# podfm.net
KiCad netlist of a schematic drawn in EAGLE
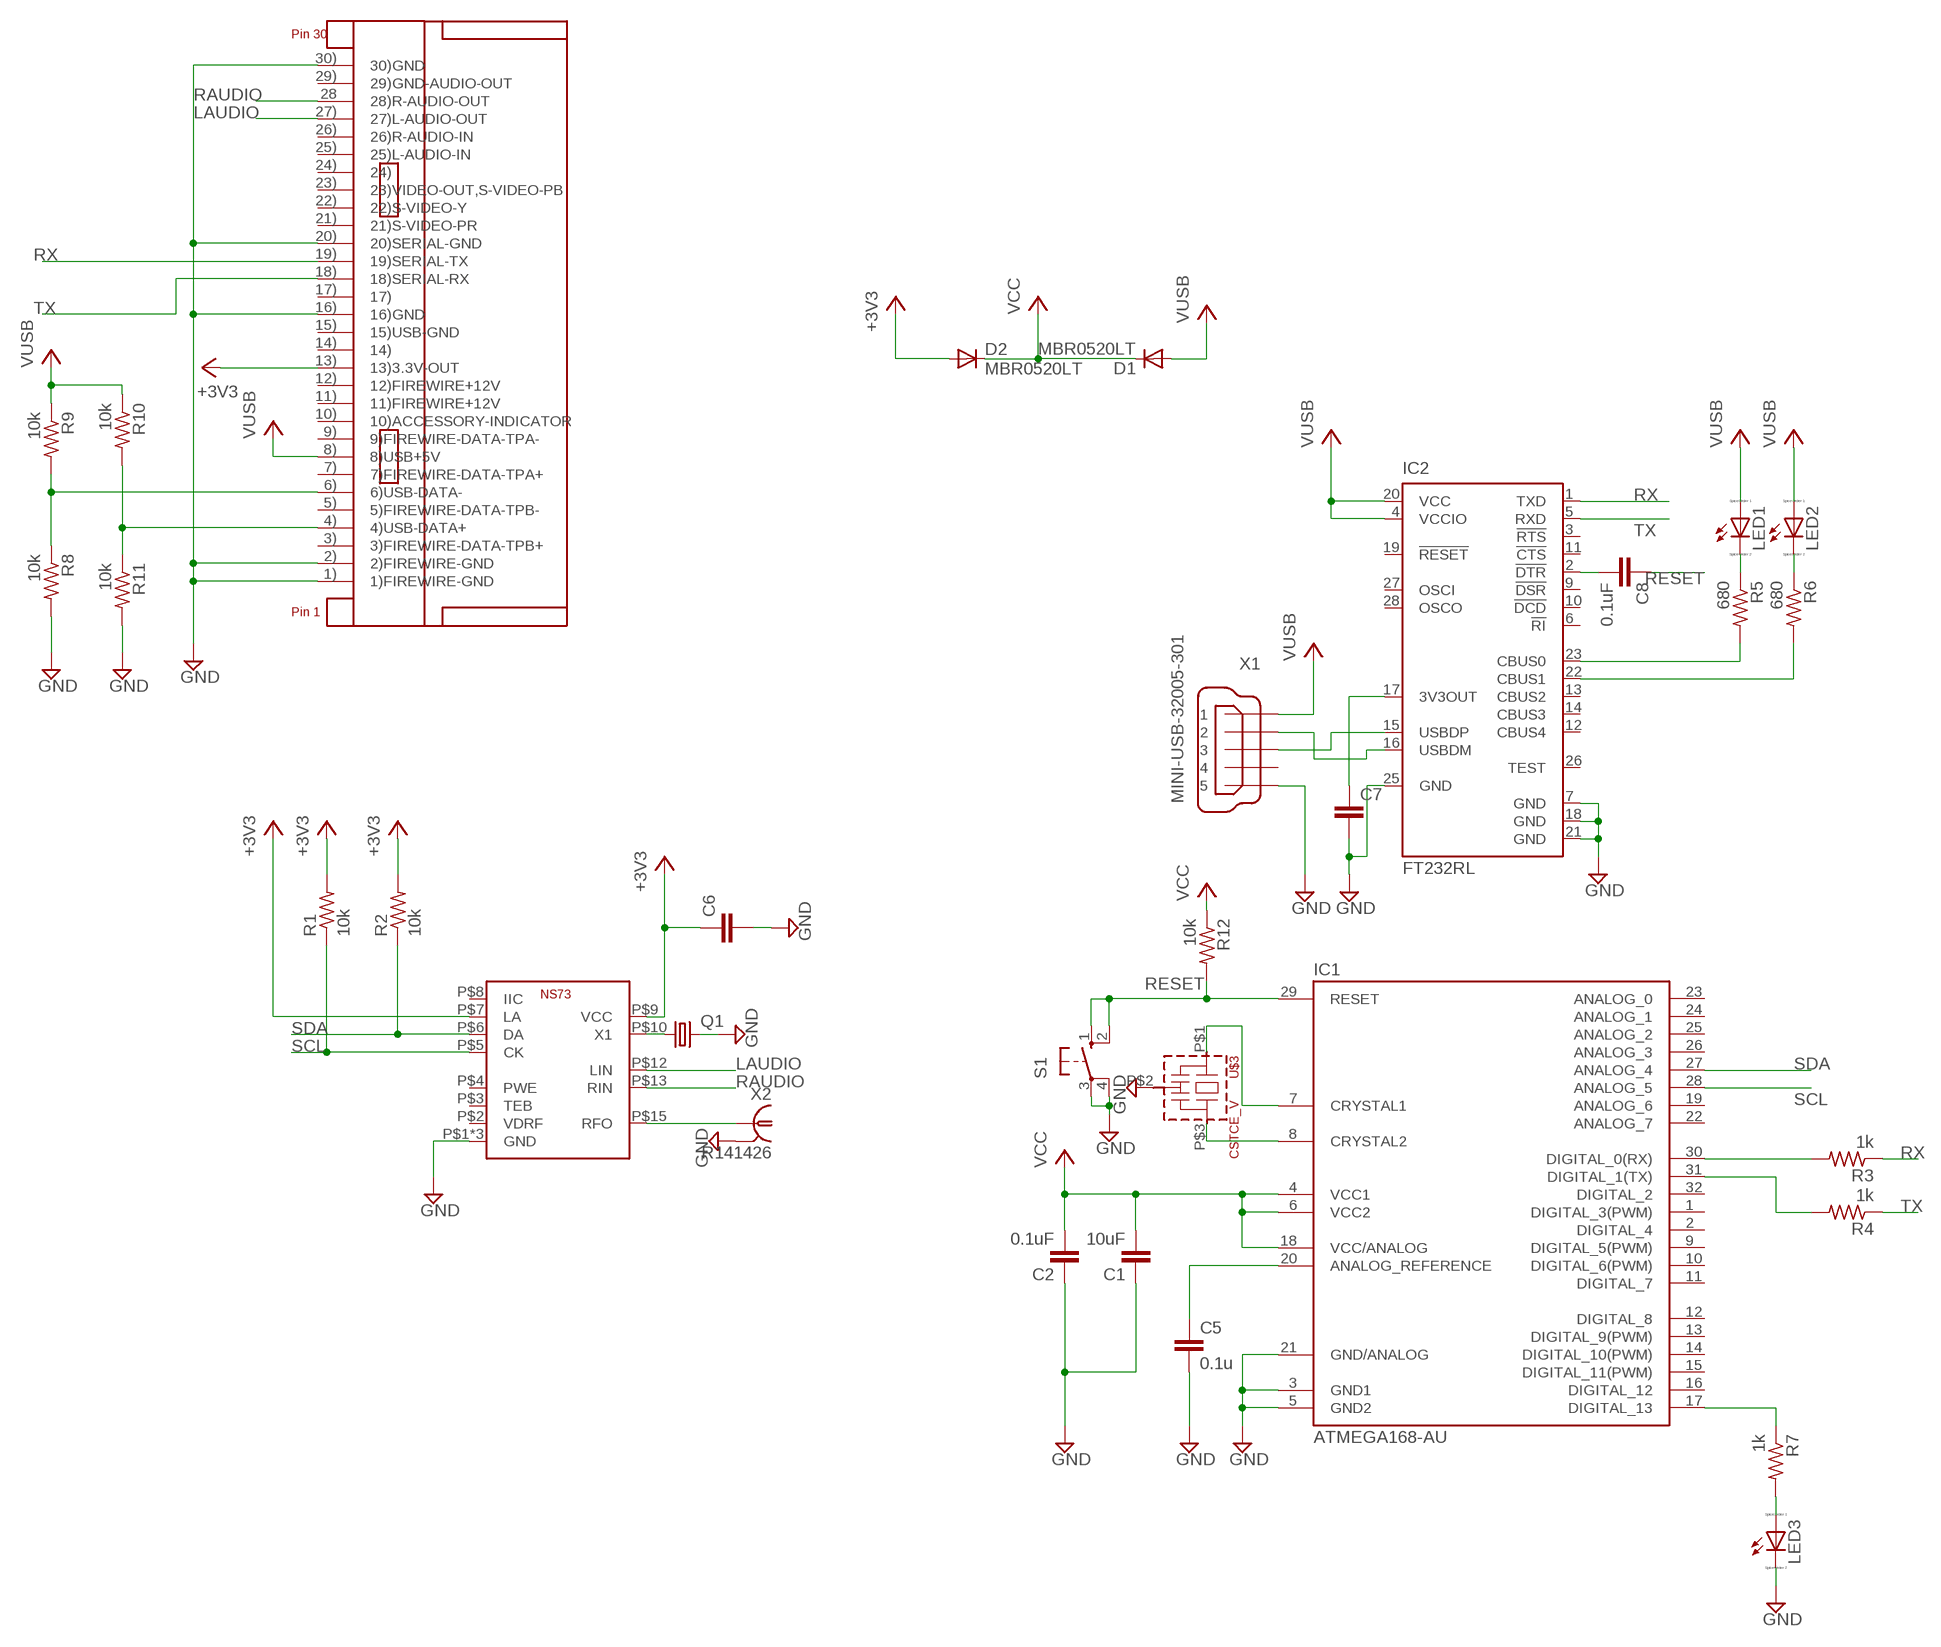
[diagram p0: schematic, sheet 1]

(export (version "E")
  (design (tool "Eeschema 10.0.6"))
  (components
    (comp (ref "C1")
      (value "10uF")
      (footprint "eagle-import:C1206")
      (libsource (lib "eagle-import") (part "C-EUC1206"))
    )
    (comp (ref "C2")
      (value "0.1uF")
      (footprint "eagle-import:C1206")
      (libsource (lib "eagle-import") (part "C-EUC1206"))
    )
    (comp (ref "C5")
      (value "0.1u")
      (footprint "eagle-import:C1206")
      (libsource (lib "eagle-import") (part "C-EUC1206"))
    )
    (comp (ref "C6")
      (value "C-EUC1206")
      (footprint "eagle-import:C1206")
      (libsource (lib "eagle-import") (part "C-EUC1206"))
    )
    (comp (ref "C7")
      (value "C-EUC1206")
      (footprint "eagle-import:C1206")
      (libsource (lib "eagle-import") (part "C-EUC1206"))
    )
    (comp (ref "C8")
      (value "0.1uF")
      (footprint "eagle-import:C1206")
      (libsource (lib "eagle-import") (part "C-EUC1206"))
    )
    (comp (ref "D1")
      (value "MBR0520LT")
      (footprint "eagle-import:SOD123")
      (libsource (lib "eagle-import") (part "MBR0520LT"))
    )
    (comp (ref "D2")
      (value "MBR0520LT")
      (footprint "eagle-import:SOD123")
      (libsource (lib "eagle-import") (part "MBR0520LT"))
    )
    (comp (ref "IC1")
      (value "ATMEGA168-AU")
      (footprint "eagle-import:TQFP32-08")
      (libsource (lib "eagle-import") (part "ATMEGA168-AU"))
    )
    (comp (ref "IC2")
      (value "FT232RL")
      (footprint "eagle-import:SSOP28")
      (libsource (lib "eagle-import") (part "FT232RL"))
    )
    (comp (ref "LED1")
      (value "LED_ESML0603")
      (footprint "eagle-import:LED_SML0603")
      (libsource (lib "eagle-import") (part "LED_ESML0603"))
    )
    (comp (ref "LED2")
      (value "LED_ESML0603")
      (footprint "eagle-import:LED_SML0603")
      (libsource (lib "eagle-import") (part "LED_ESML0603"))
    )
    (comp (ref "LED3")
      (value "LED_ESML0603")
      (footprint "eagle-import:LED_SML0603")
      (libsource (lib "eagle-import") (part "LED_ESML0603"))
    )
    (comp (ref "Q1")
      (value "CRYSTALTC26H")
      (footprint "eagle-import:TC26H")
      (libsource (lib "eagle-import") (part "CRYSTALTC26H"))
    )
    (comp (ref "R1")
      (value "10k")
      (footprint "eagle-import:R1206")
      (libsource (lib "eagle-import") (part "R-US_R1206"))
    )
    (comp (ref "R2")
      (value "10k")
      (footprint "eagle-import:R1206")
      (libsource (lib "eagle-import") (part "R-US_R1206"))
    )
    (comp (ref "R3")
      (value "1k")
      (footprint "eagle-import:R1206")
      (libsource (lib "eagle-import") (part "R-US_R1206"))
    )
    (comp (ref "R4")
      (value "1k")
      (footprint "eagle-import:R1206")
      (libsource (lib "eagle-import") (part "R-US_R1206"))
    )
    (comp (ref "R5")
      (value "680")
      (footprint "eagle-import:R0805")
      (libsource (lib "eagle-import") (part "R-US_R0805"))
    )
    (comp (ref "R6")
      (value "680")
      (footprint "eagle-import:R0805")
      (libsource (lib "eagle-import") (part "R-US_R0805"))
    )
    (comp (ref "R7")
      (value "1k")
      (footprint "eagle-import:R1206")
      (libsource (lib "eagle-import") (part "R-US_R1206"))
    )
    (comp (ref "R8")
      (value "10k")
      (footprint "eagle-import:R1206")
      (libsource (lib "eagle-import") (part "R-US_R1206"))
    )
    (comp (ref "R9")
      (value "10k")
      (footprint "eagle-import:R1206")
      (libsource (lib "eagle-import") (part "R-US_R1206"))
    )
    (comp (ref "R10")
      (value "10k")
      (footprint "eagle-import:R1206")
      (libsource (lib "eagle-import") (part "R-US_R1206"))
    )
    (comp (ref "R11")
      (value "10k")
      (footprint "eagle-import:R1206")
      (libsource (lib "eagle-import") (part "R-US_R1206"))
    )
    (comp (ref "R12")
      (value "10k")
      (footprint "eagle-import:R1206")
      (libsource (lib "eagle-import") (part "R-US_R1206"))
    )
    (comp (ref "S1")
      (value "10-XX")
      (footprint "eagle-import:B3F-10XX")
      (fields (field (name "MPN") "B3F-1000"))
      (libsource (lib "eagle-import") (part "10-XX"))
    )
    (comp (ref "U$1")
      (value "NS73")
      (footprint "eagle-import:NS73")
      (libsource (lib "eagle-import") (part "NS73"))
    )
    (comp (ref "U$2")
      (value "IPOD-DOCK-CONNECTOR")
      (footprint "eagle-import:IPOD_CONNECTOR")
      (libsource (lib "eagle-import") (part "IPOD-DOCK-CONNECTOR"))
    )
    (comp (ref "U$3")
      (value "CSTCE_V")
      (footprint "eagle-import:CSTCE_V")
      (libsource (lib "eagle-import") (part "CSTCE_V"))
    )
    (comp (ref "X1")
      (value "MINI-USB-32005-301")
      (footprint "eagle-import:32005-301")
      (libsource (lib "eagle-import") (part "MINI-USB-32005-301"))
    )
    (comp (ref "X2")
      (value "R141426")
      (footprint "eagle-import:R141426")
      (fields (field (name "MF") "FARNELL") (field (name "MPN") "R141426161"))
      (libsource (lib "eagle-import") (part "R141426"))
    )
  )
  (nets
    (net (code "1") (name "+3V3") (class "Default")
      (node (ref "C6") (pin "1") (pinfunction "1_1") (pintype "passive"))
      (node (ref "D2") (pin "A") (pinfunction "A_A") (pintype "passive"))
      (node (ref "R1") (pin "2") (pinfunction "2_2") (pintype "passive"))
      (node (ref "R2") (pin "2") (pinfunction "2_2") (pintype "passive"))
      (node (ref "U$1") (pin "P$7") (pinfunction "LA_P$7") (pintype "bidirectional"))
      (node (ref "U$1") (pin "P$9") (pinfunction "VCC_P$9") (pintype "bidirectional"))
      (node (ref "U$2") (pin "13)") (pinfunction "13)3.3V-OUT_13)") (pintype "bidirectional"))
    )
    (net (code "2") (name "/LAUDIO") (class "Default")
      (node (ref "U$1") (pin "P$12") (pinfunction "LIN_P$12") (pintype "bidirectional"))
      (node (ref "U$2") (pin "27)") (pinfunction "27)L-AUDIO-OUT_27)") (pintype "bidirectional"))
    )
    (net (code "3") (name "/RAUDIO") (class "Default")
      (node (ref "U$1") (pin "P$13") (pinfunction "RIN_P$13") (pintype "bidirectional"))
      (node (ref "U$2") (pin "28") (pinfunction "28)R-AUDIO-OUT_28") (pintype "bidirectional"))
    )
    (net (code "4") (name "/RESET") (class "Default")
      (node (ref "C8") (pin "1") (pinfunction "1_1") (pintype "passive"))
      (node (ref "IC1") (pin "29") (pinfunction "RESET_29") (pintype "bidirectional"))
      (node (ref "R12") (pin "2") (pinfunction "2_2") (pintype "passive"))
      (node (ref "S1") (pin "1") (pinfunction "S_1") (pintype "passive"))
      (node (ref "S1") (pin "2") (pinfunction "S1_2") (pintype "passive"))
    )
    (net (code "5") (name "/RX") (class "Default")
      (node (ref "IC2") (pin "1") (pinfunction "TXD_1") (pintype "output"))
      (node (ref "R3") (pin "1") (pinfunction "1_1") (pintype "passive"))
      (node (ref "U$2") (pin "19)") (pinfunction "19)SERIAL-TX_19)") (pintype "bidirectional"))
    )
    (net (code "6") (name "/SCL") (class "Default")
      (node (ref "IC1") (pin "28") (pinfunction "ANALOG_5_28") (pintype "bidirectional"))
      (node (ref "R1") (pin "1") (pinfunction "1_1") (pintype "passive"))
      (node (ref "U$1") (pin "P$5") (pinfunction "CK_P$5") (pintype "bidirectional"))
    )
    (net (code "7") (name "/SDA") (class "Default")
      (node (ref "IC1") (pin "27") (pinfunction "ANALOG_4_27") (pintype "bidirectional"))
      (node (ref "R2") (pin "1") (pinfunction "1_1") (pintype "passive"))
      (node (ref "U$1") (pin "P$6") (pinfunction "DA_P$6") (pintype "bidirectional"))
    )
    (net (code "8") (name "/TX") (class "Default")
      (node (ref "IC2") (pin "5") (pinfunction "RXD_5") (pintype "input"))
      (node (ref "R4") (pin "1") (pinfunction "1_1") (pintype "passive"))
      (node (ref "U$2") (pin "18)") (pinfunction "18)SERIAL-RX_18)") (pintype "bidirectional"))
    )
    (net (code "9") (name "GND") (class "Default")
      (node (ref "C1") (pin "1") (pinfunction "1_1") (pintype "passive"))
      (node (ref "C2") (pin "1") (pinfunction "1_1") (pintype "passive"))
      (node (ref "C5") (pin "2") (pinfunction "2_2") (pintype "passive"))
      (node (ref "C6") (pin "2") (pinfunction "2_2") (pintype "passive"))
      (node (ref "C7") (pin "2") (pinfunction "2_2") (pintype "passive"))
      (node (ref "IC1") (pin "21") (pinfunction "GND/ANALOG_21") (pintype "power_in"))
      (node (ref "IC1") (pin "3") (pinfunction "GND1_3") (pintype "power_in"))
      (node (ref "IC1") (pin "5") (pinfunction "GND2_5") (pintype "power_in"))
      (node (ref "IC2") (pin "18") (pinfunction "GND_18") (pintype "power_in"))
      (node (ref "IC2") (pin "21") (pinfunction "GND_21") (pintype "power_in"))
      (node (ref "IC2") (pin "25") (pinfunction "GND_25") (pintype "power_in"))
      (node (ref "IC2") (pin "7") (pinfunction "GND_7") (pintype "power_in"))
      (node (ref "LED3") (pin "C") (pinfunction "C_C") (pintype "passive"))
      (node (ref "Q1") (pin "2") (pinfunction "2_2") (pintype "passive"))
      (node (ref "R11") (pin "2") (pinfunction "2_2") (pintype "passive"))
      (node (ref "R8") (pin "2") (pinfunction "2_2") (pintype "passive"))
      (node (ref "S1") (pin "3") (pinfunction "P_3") (pintype "passive"))
      (node (ref "S1") (pin "4") (pinfunction "P1_4") (pintype "passive"))
      (node (ref "U$1") (pin "P$1") (pinfunction "GND_P$1") (pintype "bidirectional"))
      (node (ref "U$1") (pin "P$11") (pinfunction "GND_P$11") (pintype "bidirectional"))
      (node (ref "U$1") (pin "P$14") (pinfunction "GND_P$14") (pintype "bidirectional"))
      (node (ref "U$2") (pin "1)") (pinfunction "1)FIREWIRE-GND_1)") (pintype "bidirectional"))
      (node (ref "U$2") (pin "16)") (pinfunction "16)GND_16)") (pintype "bidirectional"))
      (node (ref "U$2") (pin "2)") (pinfunction "2)FIREWIRE-GND_2)") (pintype "bidirectional"))
      (node (ref "U$2") (pin "20)") (pinfunction "20)SERIAL-GND_20)") (pintype "bidirectional"))
      (node (ref "U$2") (pin "30)") (pinfunction "30)GND_30)") (pintype "bidirectional"))
      (node (ref "U$3") (pin "P$2") (pinfunction "VSS_P$2") (pintype "power_in"))
      (node (ref "X1") (pin "5") (pinfunction "5_5") (pintype "passive"))
      (node (ref "X1") (pin "M1") (pinfunction "5_M1") (pintype "passive"))
      (node (ref "X1") (pin "M2") (pinfunction "5_M2") (pintype "passive"))
      (node (ref "X1") (pin "M3") (pinfunction "5_M3") (pintype "passive"))
      (node (ref "X1") (pin "M4") (pinfunction "5_M4") (pintype "passive"))
      (node (ref "X2") (pin "2") (pinfunction "2_2") (pintype "passive"))
      (node (ref "X2") (pin "3") (pinfunction "2_3") (pintype "passive"))
      (node (ref "X2") (pin "4") (pinfunction "2_4") (pintype "passive"))
      (node (ref "X2") (pin "5") (pinfunction "2_5") (pintype "passive"))
    )
    (net (code "10") (name "Net-(IC1-ANALOG_REFERENCE)") (class "Default")
      (node (ref "C5") (pin "1") (pinfunction "1_1") (pintype "passive"))
      (node (ref "IC1") (pin "20") (pinfunction "ANALOG_REFERENCE_20") (pintype "passive"))
    )
    (net (code "11") (name "Net-(IC1-CRYSTAL1)") (class "Default")
      (node (ref "IC1") (pin "7") (pinfunction "CRYSTAL1_7") (pintype "bidirectional"))
      (node (ref "U$3") (pin "P$1") (pinfunction "1_P$1") (pintype "output"))
    )
    (net (code "12") (name "Net-(IC1-CRYSTAL2)") (class "Default")
      (node (ref "IC1") (pin "8") (pinfunction "CRYSTAL2_8") (pintype "bidirectional"))
      (node (ref "U$3") (pin "P$3") (pinfunction "3_P$3") (pintype "input"))
    )
    (net (code "13") (name "Net-(IC1-DIGITAL_0(RX))") (class "Default")
      (node (ref "IC1") (pin "30") (pinfunction "DIGITAL_0(RX)_30") (pintype "bidirectional"))
      (node (ref "R3") (pin "2") (pinfunction "2_2") (pintype "passive"))
    )
    (net (code "14") (name "Net-(IC1-DIGITAL_1(TX))") (class "Default")
      (node (ref "IC1") (pin "31") (pinfunction "DIGITAL_1(TX)_31") (pintype "bidirectional"))
      (node (ref "R4") (pin "2") (pinfunction "2_2") (pintype "passive"))
    )
    (net (code "15") (name "Net-(IC1-DIGITAL_13)") (class "Default")
      (node (ref "IC1") (pin "17") (pinfunction "DIGITAL_13_17") (pintype "bidirectional"))
      (node (ref "R7") (pin "1") (pinfunction "1_1") (pintype "passive"))
    )
    (net (code "16") (name "Net-(IC2-3V3OUT)") (class "Default")
      (node (ref "C7") (pin "1") (pinfunction "1_1") (pintype "passive"))
      (node (ref "IC2") (pin "17") (pinfunction "3V3OUT_17") (pintype "output"))
    )
    (net (code "17") (name "Net-(IC2-CBUS0)") (class "Default")
      (node (ref "IC2") (pin "23") (pinfunction "CBUS0_23") (pintype "bidirectional"))
      (node (ref "R5") (pin "2") (pinfunction "2_2") (pintype "passive"))
    )
    (net (code "18") (name "Net-(IC2-CBUS1)") (class "Default")
      (node (ref "IC2") (pin "22") (pinfunction "CBUS1_22") (pintype "bidirectional"))
      (node (ref "R6") (pin "2") (pinfunction "2_2") (pintype "passive"))
    )
    (net (code "19") (name "Net-(IC2-USBDM)") (class "Default")
      (node (ref "IC2") (pin "16") (pinfunction "USBDM_16") (pintype "bidirectional"))
      (node (ref "X1") (pin "2") (pinfunction "2_2") (pintype "passive"))
    )
    (net (code "20") (name "Net-(IC2-USBDP)") (class "Default")
      (node (ref "IC2") (pin "15") (pinfunction "USBDP_15") (pintype "bidirectional"))
      (node (ref "X1") (pin "3") (pinfunction "3_3") (pintype "passive"))
    )
    (net (code "21") (name "Net-(IC2-~{DTR})") (class "Default")
      (node (ref "C8") (pin "2") (pinfunction "2_2") (pintype "passive"))
      (node (ref "IC2") (pin "2") (pinfunction "~{DTR}_2") (pintype "output"))
    )
    (net (code "22") (name "Net-(LED1-PadC)") (class "Default")
      (node (ref "LED1") (pin "C") (pinfunction "C_C") (pintype "passive"))
      (node (ref "R5") (pin "1") (pinfunction "1_1") (pintype "passive"))
    )
    (net (code "23") (name "Net-(LED2-PadC)") (class "Default")
      (node (ref "LED2") (pin "C") (pinfunction "C_C") (pintype "passive"))
      (node (ref "R6") (pin "1") (pinfunction "1_1") (pintype "passive"))
    )
    (net (code "24") (name "Net-(LED3-PadA)") (class "Default")
      (node (ref "LED3") (pin "A") (pinfunction "A_A") (pintype "passive"))
      (node (ref "R7") (pin "2") (pinfunction "2_2") (pintype "passive"))
    )
    (net (code "25") (name "Net-(U$1-RFO)") (class "Default")
      (node (ref "U$1") (pin "P$15") (pinfunction "RFO_P$15") (pintype "bidirectional"))
      (node (ref "X2") (pin "1") (pinfunction "1_1") (pintype "passive"))
    )
    (net (code "26") (name "Net-(U$1-X1)") (class "Default")
      (node (ref "Q1") (pin "1") (pinfunction "1_1") (pintype "passive"))
      (node (ref "U$1") (pin "P$10") (pinfunction "X1_P$10") (pintype "bidirectional"))
    )
    (net (code "27") (name "Net-(U$2-4)USB-DATA+)") (class "Default")
      (node (ref "R10") (pin "2") (pinfunction "2_2") (pintype "passive"))
      (node (ref "R11") (pin "1") (pinfunction "1_1") (pintype "passive"))
      (node (ref "U$2") (pin "4)") (pinfunction "4)USB-DATA+_4)") (pintype "bidirectional"))
    )
    (net (code "28") (name "Net-(U$2-6)USB-DATA-)") (class "Default")
      (node (ref "R8") (pin "1") (pinfunction "1_1") (pintype "passive"))
      (node (ref "R9") (pin "2") (pinfunction "2_2") (pintype "passive"))
      (node (ref "U$2") (pin "6)") (pinfunction "6)USB-DATA-_6)") (pintype "bidirectional"))
    )
    (net (code "29") (name "VCC") (class "Default")
      (node (ref "C1") (pin "2") (pinfunction "2_2") (pintype "passive"))
      (node (ref "C2") (pin "2") (pinfunction "2_2") (pintype "passive"))
      (node (ref "D1") (pin "C") (pinfunction "C_C") (pintype "passive"))
      (node (ref "D2") (pin "C") (pinfunction "C_C") (pintype "passive"))
      (node (ref "IC1") (pin "18") (pinfunction "VCC/ANALOG_18") (pintype "passive"))
      (node (ref "IC1") (pin "4") (pinfunction "VCC1_4") (pintype "power_in"))
      (node (ref "IC1") (pin "6") (pinfunction "VCC2_6") (pintype "power_in"))
      (node (ref "R12") (pin "1") (pinfunction "1_1") (pintype "passive"))
    )
    (net (code "30") (name "VUSB") (class "Default")
      (node (ref "D1") (pin "A") (pinfunction "A_A") (pintype "passive"))
      (node (ref "IC2") (pin "20") (pinfunction "VCC_20") (pintype "power_in"))
      (node (ref "IC2") (pin "4") (pinfunction "VCCIO_4") (pintype "power_in"))
      (node (ref "LED1") (pin "A") (pinfunction "A_A") (pintype "passive"))
      (node (ref "LED2") (pin "A") (pinfunction "A_A") (pintype "passive"))
      (node (ref "R10") (pin "1") (pinfunction "1_1") (pintype "passive"))
      (node (ref "R9") (pin "1") (pinfunction "1_1") (pintype "passive"))
      (node (ref "U$2") (pin "8)") (pinfunction "8)USB+5V_8)") (pintype "bidirectional"))
      (node (ref "X1") (pin "1") (pinfunction "1_1") (pintype "passive"))
    )
    (net (code "31") (name "unconnected-(IC1-ANALOG_0-Pad23)") (class "Default")
      (node (ref "IC1") (pin "23") (pinfunction "ANALOG_0_23") (pintype "bidirectional"))
    )
    (net (code "32") (name "unconnected-(IC1-ANALOG_1-Pad24)") (class "Default")
      (node (ref "IC1") (pin "24") (pinfunction "ANALOG_1_24") (pintype "bidirectional"))
    )
    (net (code "33") (name "unconnected-(IC1-ANALOG_2-Pad25)") (class "Default")
      (node (ref "IC1") (pin "25") (pinfunction "ANALOG_2_25") (pintype "bidirectional"))
    )
    (net (code "34") (name "unconnected-(IC1-ANALOG_3-Pad26)") (class "Default")
      (node (ref "IC1") (pin "26") (pinfunction "ANALOG_3_26") (pintype "bidirectional"))
    )
    (net (code "35") (name "unconnected-(IC1-ANALOG_6-Pad19)") (class "Default")
      (node (ref "IC1") (pin "19") (pinfunction "ANALOG_6_19") (pintype "passive"))
    )
    (net (code "36") (name "unconnected-(IC1-ANALOG_7-Pad22)") (class "Default")
      (node (ref "IC1") (pin "22") (pinfunction "ANALOG_7_22") (pintype "passive"))
    )
    (net (code "37") (name "unconnected-(IC1-DIGITAL_2-Pad32)") (class "Default")
      (node (ref "IC1") (pin "32") (pinfunction "DIGITAL_2_32") (pintype "bidirectional"))
    )
    (net (code "38") (name "unconnected-(IC1-DIGITAL_3(PWM)-Pad1)") (class "Default")
      (node (ref "IC1") (pin "1") (pinfunction "DIGITAL_3(PWM)_1") (pintype "bidirectional"))
    )
    (net (code "39") (name "unconnected-(IC1-DIGITAL_4-Pad2)") (class "Default")
      (node (ref "IC1") (pin "2") (pinfunction "DIGITAL_4_2") (pintype "bidirectional"))
    )
    (net (code "40") (name "unconnected-(IC1-DIGITAL_5(PWM)-Pad9)") (class "Default")
      (node (ref "IC1") (pin "9") (pinfunction "DIGITAL_5(PWM)_9") (pintype "bidirectional"))
    )
    (net (code "41") (name "unconnected-(IC1-DIGITAL_6(PWM)-Pad10)") (class "Default")
      (node (ref "IC1") (pin "10") (pinfunction "DIGITAL_6(PWM)_10") (pintype "bidirectional"))
    )
    (net (code "42") (name "unconnected-(IC1-DIGITAL_7-Pad11)") (class "Default")
      (node (ref "IC1") (pin "11") (pinfunction "DIGITAL_7_11") (pintype "bidirectional"))
    )
    (net (code "43") (name "unconnected-(IC1-DIGITAL_8-Pad12)") (class "Default")
      (node (ref "IC1") (pin "12") (pinfunction "DIGITAL_8_12") (pintype "bidirectional"))
    )
    (net (code "44") (name "unconnected-(IC1-DIGITAL_9(PWM)-Pad13)") (class "Default")
      (node (ref "IC1") (pin "13") (pinfunction "DIGITAL_9(PWM)_13") (pintype "bidirectional"))
    )
    (net (code "45") (name "unconnected-(IC1-DIGITAL_10(PWM)-Pad14)") (class "Default")
      (node (ref "IC1") (pin "14") (pinfunction "DIGITAL_10(PWM)_14") (pintype "bidirectional"))
    )
    (net (code "46") (name "unconnected-(IC1-DIGITAL_11(PWM)-Pad15)") (class "Default")
      (node (ref "IC1") (pin "15") (pinfunction "DIGITAL_11(PWM)_15") (pintype "bidirectional"))
    )
    (net (code "47") (name "unconnected-(IC1-DIGITAL_12-Pad16)") (class "Default")
      (node (ref "IC1") (pin "16") (pinfunction "DIGITAL_12_16") (pintype "bidirectional"))
    )
    (net (code "48") (name "unconnected-(IC2-CBUS2-Pad13)") (class "Default")
      (node (ref "IC2") (pin "13") (pinfunction "CBUS2_13") (pintype "bidirectional"))
    )
    (net (code "49") (name "unconnected-(IC2-CBUS3-Pad14)") (class "Default")
      (node (ref "IC2") (pin "14") (pinfunction "CBUS3_14") (pintype "bidirectional"))
    )
    (net (code "50") (name "unconnected-(IC2-CBUS4-Pad12)") (class "Default")
      (node (ref "IC2") (pin "12") (pinfunction "CBUS4_12") (pintype "bidirectional"))
    )
    (net (code "51") (name "unconnected-(IC2-OSCI-Pad27)") (class "Default")
      (node (ref "IC2") (pin "27") (pinfunction "OSCI_27") (pintype "input"))
    )
    (net (code "52") (name "unconnected-(IC2-OSCO-Pad28)") (class "Default")
      (node (ref "IC2") (pin "28") (pinfunction "OSCO_28") (pintype "output"))
    )
    (net (code "53") (name "unconnected-(IC2-TEST-Pad26)") (class "Default")
      (node (ref "IC2") (pin "26") (pinfunction "TEST_26") (pintype "input"))
    )
    (net (code "54") (name "unconnected-(IC2-~{CTS}-Pad11)") (class "Default")
      (node (ref "IC2") (pin "11") (pinfunction "~{CTS}_11") (pintype "input"))
    )
    (net (code "55") (name "unconnected-(IC2-~{DCD}-Pad10)") (class "Default")
      (node (ref "IC2") (pin "10") (pinfunction "~{DCD}_10") (pintype "input"))
    )
    (net (code "56") (name "unconnected-(IC2-~{DSR}-Pad9)") (class "Default")
      (node (ref "IC2") (pin "9") (pinfunction "~{DSR}_9") (pintype "input"))
    )
    (net (code "57") (name "unconnected-(IC2-~{RESET}-Pad19)") (class "Default")
      (node (ref "IC2") (pin "19") (pinfunction "~{RESET}_19") (pintype "input"))
    )
    (net (code "58") (name "unconnected-(IC2-~{RI}-Pad6)") (class "Default")
      (node (ref "IC2") (pin "6") (pinfunction "~{RI}_6") (pintype "input"))
    )
    (net (code "59") (name "unconnected-(IC2-~{RTS}-Pad3)") (class "Default")
      (node (ref "IC2") (pin "3") (pinfunction "~{RTS}_3") (pintype "output"))
    )
    (net (code "60") (name "unconnected-(U$1-IIC-PadP$8)") (class "Default")
      (node (ref "U$1") (pin "P$8") (pinfunction "IIC_P$8") (pintype "bidirectional"))
    )
    (net (code "61") (name "unconnected-(U$1-PWE-PadP$4)") (class "Default")
      (node (ref "U$1") (pin "P$4") (pinfunction "PWE_P$4") (pintype "bidirectional"))
    )
    (net (code "62") (name "unconnected-(U$1-TEB-PadP$3)") (class "Default")
      (node (ref "U$1") (pin "P$3") (pinfunction "TEB_P$3") (pintype "bidirectional"))
    )
    (net (code "63") (name "unconnected-(U$1-VDRF-PadP$2)") (class "Default")
      (node (ref "U$1") (pin "P$2") (pinfunction "VDRF_P$2") (pintype "bidirectional"))
    )
    (net (code "64") (name "unconnected-(U$2-3)FIREWIRE-DATA-TPB+-Pad3))") (class "Default")
      (node (ref "U$2") (pin "3)") (pinfunction "3)FIREWIRE-DATA-TPB+_3)") (pintype "bidirectional"))
    )
    (net (code "65") (name "unconnected-(U$2-5)FIREWIRE-DATA-TPB--Pad5))") (class "Default")
      (node (ref "U$2") (pin "5)") (pinfunction "5)FIREWIRE-DATA-TPB-_5)") (pintype "bidirectional"))
    )
    (net (code "66") (name "unconnected-(U$2-7)FIREWIRE-DATA-TPA+-Pad7))") (class "Default")
      (node (ref "U$2") (pin "7)") (pinfunction "7)FIREWIRE-DATA-TPA+_7)") (pintype "bidirectional"))
    )
    (net (code "67") (name "unconnected-(U$2-9)FIREWIRE-DATA-TPA--Pad9))") (class "Default")
      (node (ref "U$2") (pin "9)") (pinfunction "9)FIREWIRE-DATA-TPA-_9)") (pintype "bidirectional"))
    )
    (net (code "68") (name "unconnected-(U$2-10)ACCESSORY-INDICATOR-Pad10))") (class "Default")
      (node (ref "U$2") (pin "10)") (pinfunction "10)ACCESSORY-INDICATOR_10)") (pintype "bidirectional"))
    )
    (net (code "69") (name "unconnected-(U$2-11)FIREWIRE+12V-Pad11))") (class "Default")
      (node (ref "U$2") (pin "11)") (pinfunction "11)FIREWIRE+12V_11)") (pintype "bidirectional"))
    )
    (net (code "70") (name "unconnected-(U$2-12)FIREWIRE+12V-Pad12))") (class "Default")
      (node (ref "U$2") (pin "12)") (pinfunction "12)FIREWIRE+12V_12)") (pintype "bidirectional"))
    )
    (net (code "71") (name "unconnected-(U$2-15)USB-GND-Pad15))") (class "Default")
      (node (ref "U$2") (pin "15)") (pinfunction "15)USB-GND_15)") (pintype "bidirectional"))
    )
    (net (code "72") (name "unconnected-(U$2-21)S-VIDEO-PR-Pad21))") (class "Default")
      (node (ref "U$2") (pin "21)") (pinfunction "21)S-VIDEO-PR_21)") (pintype "bidirectional"))
    )
    (net (code "73") (name "unconnected-(U$2-22)S-VIDEO-Y-Pad22))") (class "Default")
      (node (ref "U$2") (pin "22)") (pinfunction "22)S-VIDEO-Y_22)") (pintype "bidirectional"))
    )
    (net (code "74") (name "unconnected-(U$2-23)VIDEO-OUT,S-VIDEO-PB-Pad23))") (class "Default")
      (node (ref "U$2") (pin "23)") (pinfunction "23)VIDEO-OUT,S-VIDEO-PB_23)") (pintype "bidirectional"))
    )
    (net (code "75") (name "unconnected-(U$2-25)L-AUDIO-IN-Pad25))") (class "Default")
      (node (ref "U$2") (pin "25)") (pinfunction "25)L-AUDIO-IN_25)") (pintype "bidirectional"))
    )
    (net (code "76") (name "unconnected-(U$2-26)R-AUDIO-IN-Pad26))") (class "Default")
      (node (ref "U$2") (pin "26)") (pinfunction "26)R-AUDIO-IN_26)") (pintype "bidirectional"))
    )
    (net (code "77") (name "unconnected-(U$2-29)GND-AUDIO-OUT-Pad29))") (class "Default")
      (node (ref "U$2") (pin "29)") (pinfunction "29)GND-AUDIO-OUT_29)") (pintype "bidirectional"))
    )
    (net (code "78") (name "unconnected-(U$2-Pad14))") (class "Default")
      (node (ref "U$2") (pin "14)") (pinfunction "14)_14)") (pintype "bidirectional"))
    )
    (net (code "79") (name "unconnected-(U$2-Pad17))") (class "Default")
      (node (ref "U$2") (pin "17)") (pinfunction "17)_17)") (pintype "bidirectional"))
    )
    (net (code "80") (name "unconnected-(U$2-Pad24))") (class "Default")
      (node (ref "U$2") (pin "24)") (pinfunction "24)_24)") (pintype "bidirectional"))
    )
    (net (code "81") (name "unconnected-(X1-Pad4)") (class "Default")
      (node (ref "X1") (pin "4") (pinfunction "4_4") (pintype "passive"))
    )
  )
)
